# xlr.net
KiCad netlist of a schematic drawn in EAGLE
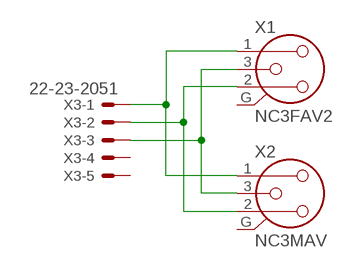
[diagram p0: schematic, sheet 1]

(export (version "E")
  (design (tool "Eeschema 10.0.6"))
  (components
    (comp (ref "X1")
      (value "NC3FAV2")
      (footprint "eagle-import:NC3FAV2")
      (fields (field (name "MF") "NEUTRIK"))
      (libsource (lib "eagle-import") (part "NC3FAV2"))
    )
    (comp (ref "X2")
      (value "NC3MAV")
      (footprint "eagle-import:NC3MAV")
      (fields (field (name "MF") "FARNELL"))
      (libsource (lib "eagle-import") (part "NC3MAV"))
    )
    (comp (ref "X3")
      (value "22-23-2051")
      (footprint "eagle-import:22-23-2051")
      (fields (field (name "MF") "MOLEX"))
      (libsource (lib "eagle-import") (part "22-23-2051"))
    )
  )
  (nets
    (net (code "1") (name "Net-(X3A-S)") (class "Default")
      (node (ref "X1") (pin "1") (pinfunction "1_1") (pintype "passive"))
      (node (ref "X2") (pin "1") (pinfunction "1_1") (pintype "passive"))
      (node (ref "X3") (pin "1") (pinfunction "S_1") (pintype "passive"))
    )
    (net (code "2") (name "Net-(X3B-S)") (class "Default")
      (node (ref "X1") (pin "2") (pinfunction "2_2") (pintype "passive"))
      (node (ref "X2") (pin "2") (pinfunction "2_2") (pintype "passive"))
      (node (ref "X3") (pin "2") (pinfunction "S_2") (pintype "passive"))
    )
    (net (code "3") (name "Net-(X3C-S)") (class "Default")
      (node (ref "X1") (pin "3") (pinfunction "3_3") (pintype "passive"))
      (node (ref "X2") (pin "3") (pinfunction "3_3") (pintype "passive"))
      (node (ref "X3") (pin "3") (pinfunction "S_3") (pintype "passive"))
    )
    (net (code "4") (name "unconnected-(X1-PadG)") (class "Default")
      (node (ref "X1") (pin "G") (pinfunction "G_G") (pintype "passive"))
    )
    (net (code "5") (name "unconnected-(X2-PadG)") (class "Default")
      (node (ref "X2") (pin "G") (pinfunction "G_G") (pintype "passive"))
    )
    (net (code "6") (name "unconnected-(X3D-S-Pad4)") (class "Default")
      (node (ref "X3") (pin "4") (pinfunction "S_4") (pintype "passive"))
    )
    (net (code "7") (name "unconnected-(X3E-S-Pad5)") (class "Default")
      (node (ref "X3") (pin "5") (pinfunction "S_5") (pintype "passive"))
    )
  )
)
